# lm2665.net
KiCad netlist of a schematic drawn in EAGLE
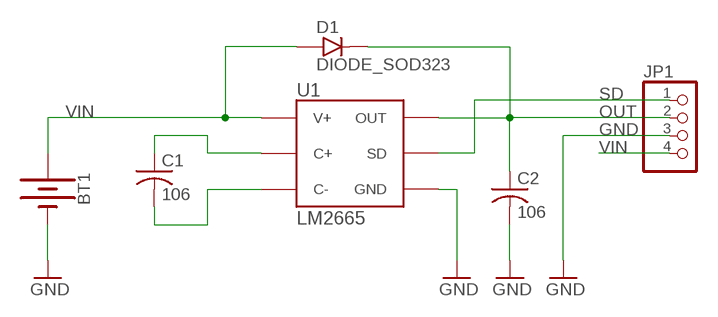
[diagram p0: schematic, sheet 1]

(export (version "E")
  (design (tool "Eeschema 10.0.6"))
  (components
    (comp (ref "BT1")
      (value "BATTERY-12MM_PTH")
      (footprint "eagle-import:BATTCON_12MM_PTH")
      (libsource (lib "eagle-import") (part "BATTERY-12MM_PTH"))
    )
    (comp (ref "C1")
      (value "106")
      (footprint "eagle-import:1206")
      (libsource (lib "eagle-import") (part "C-1206"))
    )
    (comp (ref "C2")
      (value "106")
      (footprint "eagle-import:1206")
      (libsource (lib "eagle-import") (part "C-1206"))
    )
    (comp (ref "D1")
      (value "DIODE_SOD323")
      (footprint "eagle-import:SOD-323")
      (libsource (lib "eagle-import") (part "DIODE_SOD323"))
    )
    (comp (ref "JP1")
      (value "PINHD-1X04_2.54-S")
      (footprint "eagle-import:1X04-S")
      (libsource (lib "eagle-import") (part "PINHD-1X04_2.54-S"))
    )
    (comp (ref "U1")
      (value "LM2665")
      (footprint "eagle-import:SOT23-6")
      (libsource (lib "eagle-import") (part "LM2665"))
    )
  )
  (nets
    (net (code "1") (name "/OUT") (class "Default")
      (node (ref "C2") (pin "1") (pinfunction "+_1") (pintype "passive"))
      (node (ref "D1") (pin "C") (pinfunction "C_C") (pintype "passive"))
      (node (ref "JP1") (pin "2") (pinfunction "2_2") (pintype "passive"))
      (node (ref "U1") (pin "5") (pinfunction "OUT_5") (pintype "power_in"))
    )
    (net (code "2") (name "/SD") (class "Default")
      (node (ref "JP1") (pin "1") (pinfunction "1_1") (pintype "passive"))
      (node (ref "U1") (pin "4") (pinfunction "SD_4") (pintype "bidirectional"))
    )
    (net (code "3") (name "/VIN") (class "Default")
      (node (ref "BT1") (pin "VCC@1") (pinfunction "+_VCC@1") (pintype "power_in"))
      (node (ref "D1") (pin "A") (pinfunction "A_A") (pintype "passive"))
      (node (ref "JP1") (pin "4") (pinfunction "4_4") (pintype "passive"))
      (node (ref "U1") (pin "1") (pinfunction "V+_1") (pintype "power_in"))
    )
    (net (code "4") (name "GND") (class "Default")
      (node (ref "BT1") (pin "GND") (pinfunction "-_GND") (pintype "power_in"))
      (node (ref "C2") (pin "2") (pinfunction "-_2") (pintype "passive"))
      (node (ref "JP1") (pin "3") (pinfunction "3_3") (pintype "passive"))
      (node (ref "U1") (pin "2") (pinfunction "GND_2") (pintype "bidirectional"))
    )
    (net (code "5") (name "Net-(C1-+)") (class "Default")
      (node (ref "C1") (pin "1") (pinfunction "+_1") (pintype "passive"))
      (node (ref "U1") (pin "6") (pinfunction "C+_6") (pintype "bidirectional"))
    )
    (net (code "6") (name "Net-(C1--)") (class "Default")
      (node (ref "C1") (pin "2") (pinfunction "-_2") (pintype "passive"))
      (node (ref "U1") (pin "3") (pinfunction "C-_3") (pintype "bidirectional"))
    )
  )
)
